# MDL_FUENTE_5V.net
KiCad netlist of a schematic drawn in Altium Designer
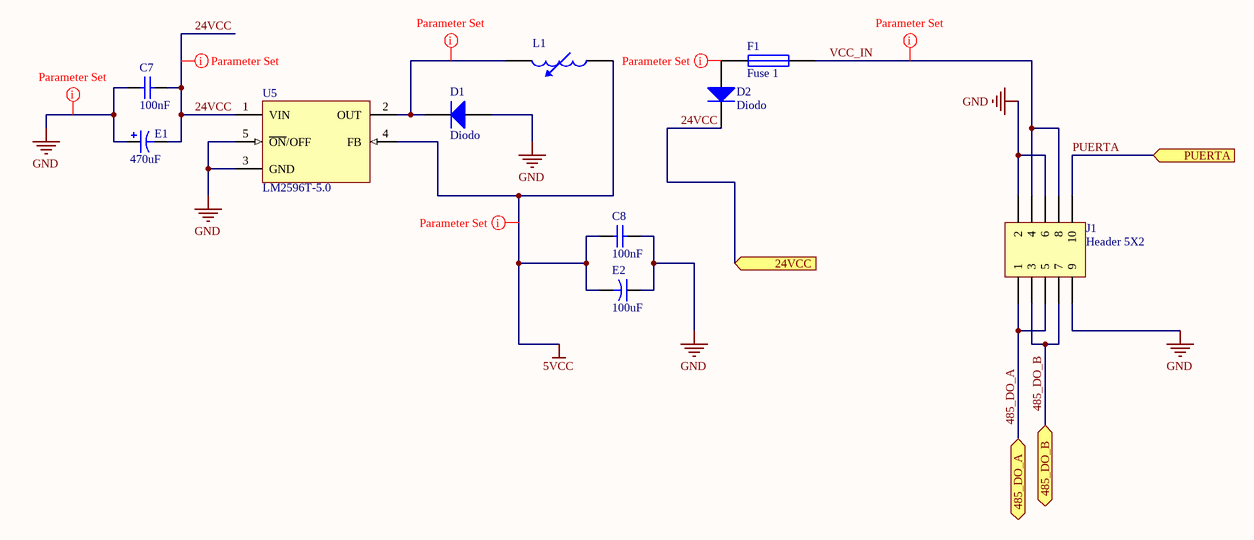
[diagram p0: MDL_FUENTE_5V.SchDoc]

(export (version "E")
  (design (tool "Eeschema 10.0.6"))
  (components
    (comp (ref "C7")
      (value "100nF")
      (footprint "VP44-2.5")
      (description "Dipped Radial Multilayer Ceramic Capacitor X7R: 220nF, 100V")
      (fields (field (name "Comment") "VP44BY224JB") (field (name "PUBLISHER") "Altium Limited"))
      (libsource (lib "Vishay Vitramon Ceramic Dipped Capacitor") (part "VP44BY224JB"))
    )
    (comp (ref "C8")
      (value "100nF")
      (footprint "VP44-2.5")
      (description "Dipped Radial Multilayer Ceramic Capacitor X7R: 220nF, 100V")
      (fields (field (name "Comment") "VP44BY224JB") (field (name "PUBLISHER") "Altium Limited"))
      (libsource (lib "Vishay Vitramon Ceramic Dipped Capacitor") (part "VP44BY224JB"))
    )
    (comp (ref "D1")
      (value "Diodo")
      (footprint "1N4000")
      (description "Diodo rectificador")
      (libsource (lib "Diodos") (part "Diodo"))
    )
    (comp (ref "D2")
      (value "Diodo")
      (footprint "1N4000")
      (description "Diodo rectificador")
      (libsource (lib "Diodos") (part "Diodo"))
    )
    (comp (ref "E1")
      (value "470uF")
      (footprint "C1000UF")
      (description "Polarized Capacitor (Radial)")
      (fields (field (name "Comment") "Cap Pol1") (field (name "PUBLISHER") "Altium Limited"))
      (libsource (lib "Miscellaneous Devices") (part "Cap Pol1"))
    )
    (comp (ref "E2")
      (value "100uF")
      (footprint "C1UF")
      (description "Capacitor")
      (fields (field (name "Comment") "Cap2") (field (name "PUBLISHER") "Altium Limited"))
      (libsource (lib "Miscellaneous Devices") (part "Cap2"))
    )
    (comp (ref "F1")
      (value "Fuse 1")
      (footprint "FUSIBLE_BUSMATIC")
      (description "Fuse")
      (fields (field (name "PUBLISHER") "Altium Limited"))
      (libsource (lib "Miscellaneous Devices") (part "Fuse 1"))
    )
    (comp (ref "J1")
      (value "Header 5X2")
      (footprint "PCBComponent_1")
      (description "Header, 5-Pin, Dual row")
      (fields (field (name "PUBLISHER") "Altium Limited"))
      (libsource (lib "Miscellaneous Connectors") (part "Header 5X2"))
    )
    (comp (ref "L1")
      (value "Inductor Adj")
      (footprint "Inductor_redondo")
      (description "Adjustable Inductor")
      (fields (field (name "PUBLISHER") "Altium Limited"))
      (libsource (lib "Miscellaneous Devices") (part "Inductor Adj"))
    )
    (comp (ref "U5")
      (value "LM2596T-5.0")
      (footprint "FP_LM2596_D_PCB")
      (description "SIMPLE SWITCHER Power Converter 150 KHz 3A Step-Down Voltage Regulator")
      (fields
        (field (name "MANUFACTURER") "National Semiconductor")
        (field (name "DIGIKEYPARTNUMBER") "LM2596T-5.0-ND")
        (field (name "PUBLISHER") "Altium Limited")
      )
      (libsource (lib "NSC Switcher") (part "LM2596T-5.0"))
    )
  )
  (nets
    (net (code "1") (name "/24VCC") (class "Default")
      (node (ref "C7") (pin "1") (pinfunction "1_1") (pintype "passive"))
      (node (ref "D2") (pin "2") (pinfunction "K_2") (pintype "passive"))
      (node (ref "E1") (pin "2") (pinfunction "2_2") (pintype "passive"))
      (node (ref "U5") (pin "1") (pinfunction "VIN_1") (pintype "power_in"))
    )
    (net (code "2") (name "/485_DO_A") (class "Default")
      (node (ref "J1") (pin "1") (pinfunction "1_1") (pintype "passive"))
      (node (ref "J1") (pin "5") (pinfunction "5_5") (pintype "passive"))
    )
    (net (code "3") (name "/485_DO_B") (class "Default")
      (node (ref "J1") (pin "3") (pinfunction "3_3") (pintype "passive"))
      (node (ref "J1") (pin "7") (pinfunction "7_7") (pintype "passive"))
    )
    (net (code "4") (name "/PUERTA") (class "Default")
      (node (ref "J1") (pin "10") (pinfunction "10_10") (pintype "passive"))
    )
    (net (code "5") (name "/VCC_IN") (class "Default")
      (node (ref "F1") (pin "2") (pinfunction "2_2") (pintype "passive"))
      (node (ref "J1") (pin "4") (pinfunction "4_4") (pintype "passive"))
      (node (ref "J1") (pin "8") (pinfunction "8_8") (pintype "passive"))
    )
    (net (code "6") (name "5VCC") (class "Default")
      (node (ref "C8") (pin "2") (pinfunction "2_2") (pintype "passive"))
      (node (ref "E2") (pin "2") (pinfunction "2_2") (pintype "passive"))
      (node (ref "L1") (pin "1") (pinfunction "1_1") (pintype "passive"))
      (node (ref "U5") (pin "4") (pinfunction "FB_4") (pintype "input"))
    )
    (net (code "7") (name "GND") (class "Default")
      (node (ref "C7") (pin "2") (pinfunction "2_2") (pintype "passive"))
      (node (ref "C8") (pin "1") (pinfunction "1_1") (pintype "passive"))
      (node (ref "D1") (pin "1") (pinfunction "A_1") (pintype "passive"))
      (node (ref "E1") (pin "1") (pinfunction "1_1") (pintype "passive"))
      (node (ref "E2") (pin "1") (pinfunction "1_1") (pintype "passive"))
      (node (ref "J1") (pin "2") (pinfunction "2_2") (pintype "passive"))
      (node (ref "J1") (pin "6") (pinfunction "6_6") (pintype "passive"))
      (node (ref "J1") (pin "9") (pinfunction "9_9") (pintype "passive"))
      (node (ref "U5") (pin "3") (pinfunction "GND_3") (pintype "power_in"))
      (node (ref "U5") (pin "5") (pinfunction "~{ON}/OFF_5") (pintype "input"))
    )
    (net (code "8") (name "Net-(D1-K)") (class "Default")
      (node (ref "D1") (pin "2") (pinfunction "K_2") (pintype "passive"))
      (node (ref "L1") (pin "2") (pinfunction "2_2") (pintype "passive"))
      (node (ref "U5") (pin "2") (pinfunction "OUT_2") (pintype "power_in"))
    )
    (net (code "9") (name "Net-(D2-A)") (class "Default")
      (node (ref "D2") (pin "1") (pinfunction "A_1") (pintype "passive"))
      (node (ref "F1") (pin "1") (pinfunction "1_1") (pintype "passive"))
    )
  )
)
